# 8_Power_Supply_Config.net
KiCad netlist of a schematic drawn in Altium Designer
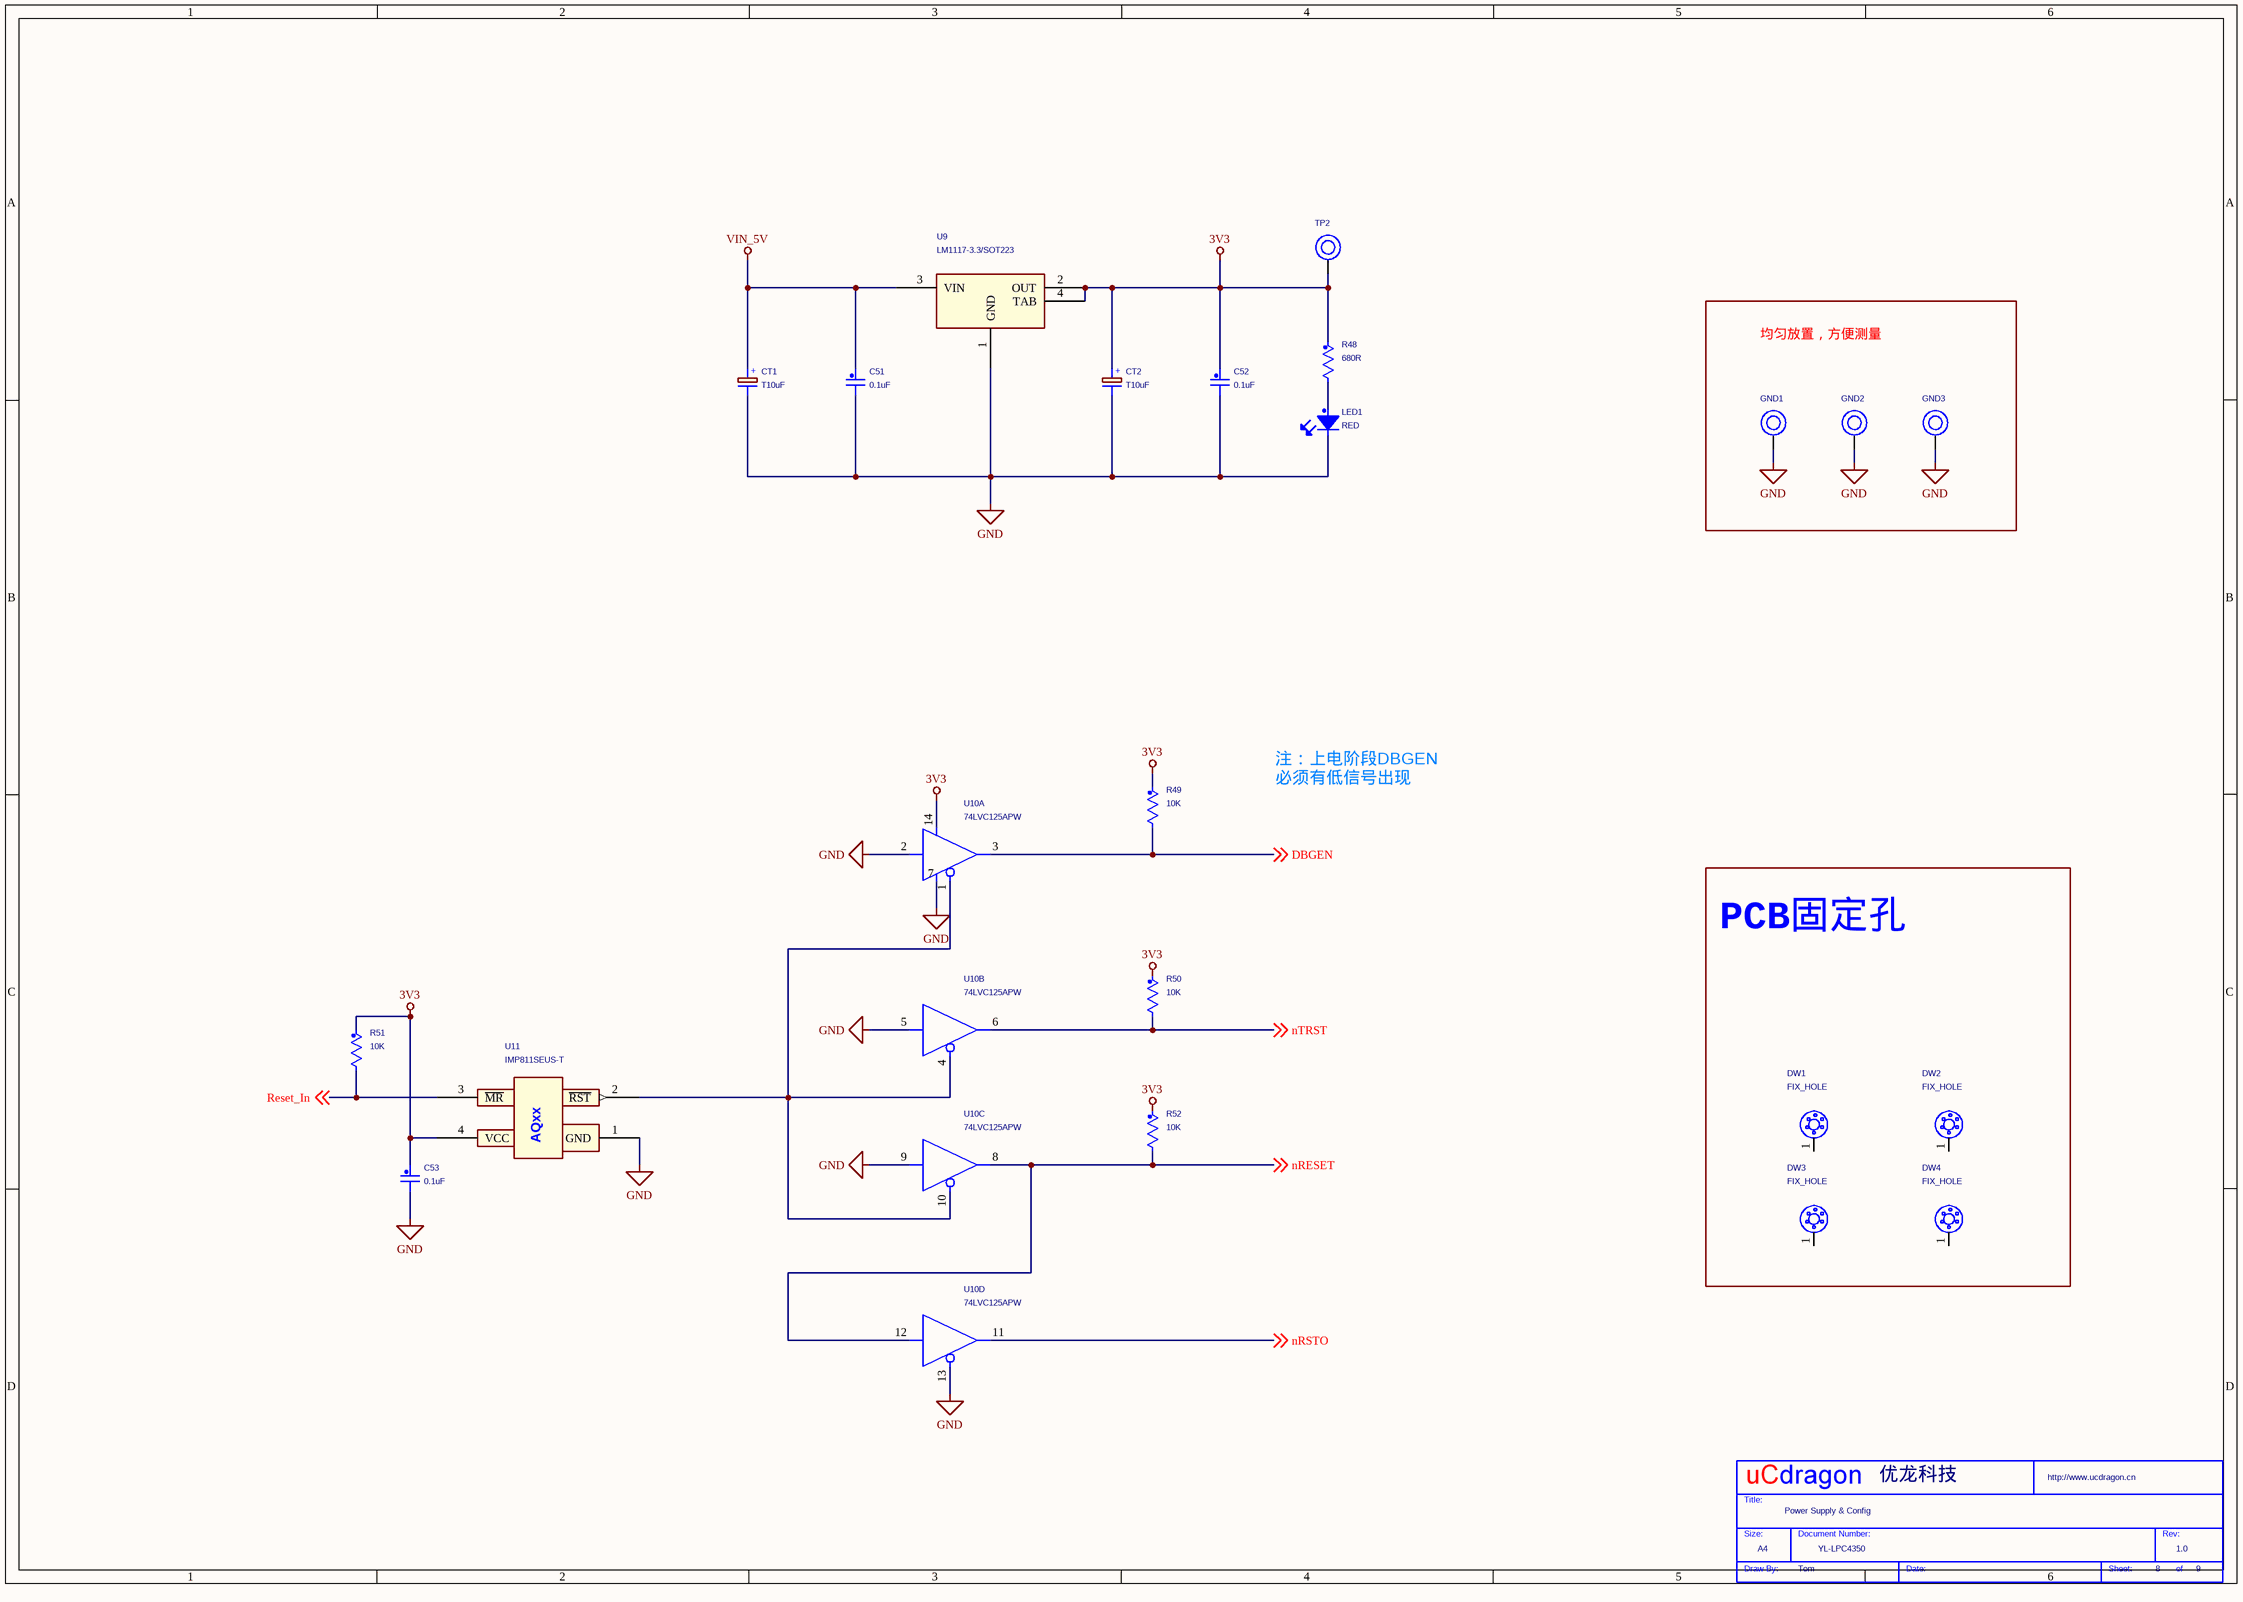
[diagram p0: 8) Power Supply,Config.SchDoc]

(export (version "E")
  (design (tool "Eeschema 10.0.6"))
  (components
    (comp (ref "C51")
      (value "0.1uF")
      (footprint "CAP0805")
      (fields (field (name "VOLTAGE") "16V"))
      (libsource (lib "*") (part "C_Generic"))
    )
    (comp (ref "C52")
      (value "0.1uF")
      (footprint "CAP0805")
      (fields (field (name "VOLTAGE") "16V"))
      (libsource (lib "*") (part "C_Generic"))
    )
    (comp (ref "C53")
      (value "0.1uF")
      (footprint "CAP0805")
      (fields (field (name "VOLTAGE") "16V"))
      (libsource (lib "*") (part "C_Generic"))
    )
    (comp (ref "CT1") (value "T10uF") (libsource (lib "*") (part "CAP PN")))
    (comp (ref "CT2") (value "T10uF") (libsource (lib "*") (part "CAP PN")))
    (comp (ref "DW1") (value "FIX_HOLE") (libsource (lib "*") (part "FIX_HOLE")))
    (comp (ref "DW2") (value "FIX_HOLE") (libsource (lib "*") (part "FIX_HOLE")))
    (comp (ref "DW3") (value "FIX_HOLE") (libsource (lib "*") (part "FIX_HOLE")))
    (comp (ref "DW4") (value "FIX_HOLE") (libsource (lib "*") (part "FIX_HOLE")))
    (comp (ref "GND1") (value "GND") (footprint "XP-TP-H0.8MM") (libsource (lib "*") (part "TestPoint-HOLE")))
    (comp (ref "GND2") (value "GND") (footprint "XP-TP-H0.8MM") (libsource (lib "*") (part "TestPoint-HOLE")))
    (comp (ref "GND3") (value "GND") (footprint "XP-TP-H0.8MM") (libsource (lib "*") (part "TestPoint-HOLE")))
    (comp (ref "LED1") (value "RED") (libsource (lib "*") (part "LED Marking Pin 1")))
    (comp (ref "R48") (value "680R") (libsource (lib "*") (part "R_Generic_Dup2")))
    (comp (ref "R49") (value "10K") (libsource (lib "*") (part "R_Generic_Dup2")))
    (comp (ref "R50") (value "10K") (libsource (lib "*") (part "R_Generic_Dup2")))
    (comp (ref "R51") (value "10K") (libsource (lib "*") (part "R_Generic_Dup2")))
    (comp (ref "R52") (value "10K") (libsource (lib "*") (part "R_Generic_Dup2")))
    (comp (ref "TP2") (value "3.3V") (footprint "XP-TP-H0.8MM") (libsource (lib "*") (part "TestPoint-HOLE")))
    (comp (ref "U9")
      (value "LM1117-3.3/SOT223")
      (footprint "XP-SOT223-3")
      (libsource (lib "*") (part "LM1117 SOT223"))
    )
    (comp (ref "U10") (value "74LVC125APW") (libsource (lib "*") (part "74HC125")))
    (comp (ref "U11") (value "IMP811SEUS-T") (libsource (lib "*") (part "IMP811SEUS-T")))
  )
  (nets
    (net (code "1") (name "3V3") (class "Default")
      (node (ref "C52") (pin "1") (pinfunction "1_1") (pintype "passive"))
      (node (ref "C53") (pin "1") (pinfunction "1_1") (pintype "passive"))
      (node (ref "CT2") (pin "1") (pinfunction "1_1") (pintype "passive"))
      (node (ref "R48") (pin "1") (pinfunction "1_1") (pintype "passive"))
      (node (ref "R49") (pin "1") (pinfunction "1_1") (pintype "passive"))
      (node (ref "R50") (pin "1") (pinfunction "1_1") (pintype "passive"))
      (node (ref "R51") (pin "1") (pinfunction "1_1") (pintype "passive"))
      (node (ref "R52") (pin "1") (pinfunction "1_1") (pintype "passive"))
      (node (ref "TP2") (pin "1") (pinfunction "1_1") (pintype "passive"))
      (node (ref "U10") (pin "14") (pinfunction "VCC_14") (pintype "passive"))
      (node (ref "U11") (pin "4") (pinfunction "VCC_4") (pintype "passive"))
      (node (ref "U9") (pin "2") (pinfunction "OUT_2") (pintype "passive"))
      (node (ref "U9") (pin "4") (pinfunction "TAB_4") (pintype "passive"))
    )
    (net (code "2") (name "DBGEN") (class "Default")
      (node (ref "R49") (pin "2") (pinfunction "2_2") (pintype "passive"))
      (node (ref "U10") (pin "3") (pinfunction "Y_3") (pintype "tri_state"))
    )
    (net (code "3") (name "GND") (class "Default")
      (node (ref "C51") (pin "2") (pinfunction "2_2") (pintype "passive"))
      (node (ref "C52") (pin "2") (pinfunction "2_2") (pintype "passive"))
      (node (ref "C53") (pin "2") (pinfunction "2_2") (pintype "passive"))
      (node (ref "CT1") (pin "2") (pinfunction "2_2") (pintype "passive"))
      (node (ref "CT2") (pin "2") (pinfunction "2_2") (pintype "passive"))
      (node (ref "GND1") (pin "1") (pinfunction "1_1") (pintype "passive"))
      (node (ref "GND2") (pin "1") (pinfunction "1_1") (pintype "passive"))
      (node (ref "GND3") (pin "1") (pinfunction "1_1") (pintype "passive"))
      (node (ref "LED1") (pin "2") (pinfunction "2_2") (pintype "passive"))
      (node (ref "U10") (pin "13") (pinfunction "OE_13") (pintype "input"))
      (node (ref "U10") (pin "2") (pinfunction "A_2") (pintype "input"))
      (node (ref "U10") (pin "5") (pinfunction "A_5") (pintype "input"))
      (node (ref "U10") (pin "7") (pinfunction "GND_7") (pintype "passive"))
      (node (ref "U10") (pin "9") (pinfunction "A_9") (pintype "input"))
      (node (ref "U11") (pin "1") (pinfunction "GND_1") (pintype "passive"))
      (node (ref "U9") (pin "1") (pinfunction "GND_1") (pintype "passive"))
    )
    (net (code "4") (name "Net-(LED1-Pad1)") (class "Default")
      (node (ref "LED1") (pin "1") (pinfunction "1_1") (pintype "passive"))
      (node (ref "R48") (pin "2") (pinfunction "2_2") (pintype "passive"))
    )
    (net (code "5") (name "Net-(U10A-OE)") (class "Default")
      (node (ref "U10") (pin "1") (pinfunction "OE_1") (pintype "input"))
      (node (ref "U10") (pin "10") (pinfunction "OE_10") (pintype "input"))
      (node (ref "U10") (pin "4") (pinfunction "OE_4") (pintype "input"))
      (node (ref "U11") (pin "2") (pinfunction "~{RST}_2") (pintype "output"))
    )
    (net (code "6") (name "Reset_In") (class "Default")
      (node (ref "R51") (pin "2") (pinfunction "2_2") (pintype "passive"))
      (node (ref "U11") (pin "3") (pinfunction "~{MR}_3") (pintype "passive"))
    )
    (net (code "7") (name "VIN_5V") (class "Default")
      (node (ref "C51") (pin "1") (pinfunction "1_1") (pintype "passive"))
      (node (ref "CT1") (pin "1") (pinfunction "1_1") (pintype "passive"))
      (node (ref "U9") (pin "3") (pinfunction "VIN_3") (pintype "passive"))
    )
    (net (code "8") (name "nRESET") (class "Default")
      (node (ref "R52") (pin "2") (pinfunction "2_2") (pintype "passive"))
      (node (ref "U10") (pin "12") (pinfunction "A_12") (pintype "input"))
      (node (ref "U10") (pin "8") (pinfunction "Y_8") (pintype "tri_state"))
    )
    (net (code "9") (name "nRSTO") (class "Default")
      (node (ref "U10") (pin "11") (pinfunction "Y_11") (pintype "tri_state"))
    )
    (net (code "10") (name "nTRST") (class "Default")
      (node (ref "R50") (pin "2") (pinfunction "2_2") (pintype "passive"))
      (node (ref "U10") (pin "6") (pinfunction "Y_6") (pintype "tri_state"))
    )
    (net (code "11") (name "unconnected-(DW1-Pad1)") (class "Default")
      (node (ref "DW1") (pin "1") (pinfunction "1_1") (pintype "passive"))
    )
    (net (code "12") (name "unconnected-(DW2-Pad1)") (class "Default")
      (node (ref "DW2") (pin "1") (pinfunction "1_1") (pintype "passive"))
    )
    (net (code "13") (name "unconnected-(DW3-Pad1)") (class "Default")
      (node (ref "DW3") (pin "1") (pinfunction "1_1") (pintype "passive"))
    )
    (net (code "14") (name "unconnected-(DW4-Pad1)") (class "Default")
      (node (ref "DW4") (pin "1") (pinfunction "1_1") (pintype "passive"))
    )
  )
)
